# MOSFET_Driver_8_24_2505D.net
KiCad netlist of a schematic drawn in EAGLE
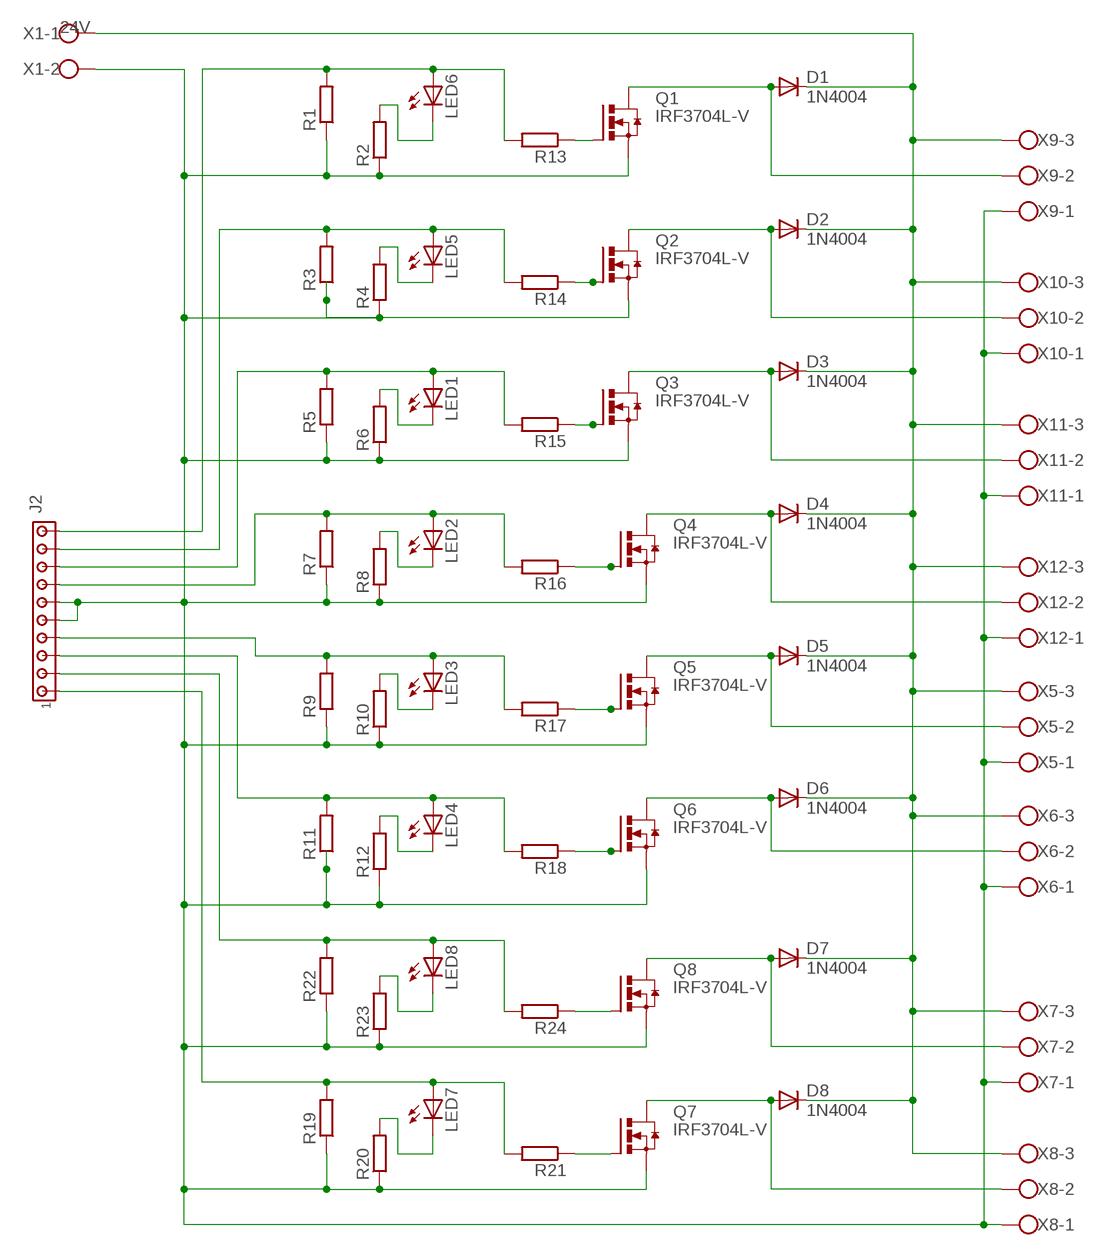
[diagram p0: schematic, sheet 1]

(export (version "E")
  (design (tool "Eeschema 10.0.6"))
  (components
    (comp (ref "D1")
      (value "1N4004")
      (footprint "eagle-import:DO41-10")
      (libsource (lib "eagle-import") (part "1N4004"))
    )
    (comp (ref "D2")
      (value "1N4004")
      (footprint "eagle-import:DO41-10")
      (libsource (lib "eagle-import") (part "1N4004"))
    )
    (comp (ref "D3")
      (value "1N4004")
      (footprint "eagle-import:DO41-10")
      (libsource (lib "eagle-import") (part "1N4004"))
    )
    (comp (ref "D4")
      (value "1N4004")
      (footprint "eagle-import:DO41-10")
      (libsource (lib "eagle-import") (part "1N4004"))
    )
    (comp (ref "D5")
      (value "1N4004")
      (footprint "eagle-import:DO41-10")
      (libsource (lib "eagle-import") (part "1N4004"))
    )
    (comp (ref "D6")
      (value "1N4004")
      (footprint "eagle-import:DO41-10")
      (libsource (lib "eagle-import") (part "1N4004"))
    )
    (comp (ref "D7")
      (value "1N4004")
      (footprint "eagle-import:DO41-10")
      (libsource (lib "eagle-import") (part "1N4004"))
    )
    (comp (ref "D8")
      (value "1N4004")
      (footprint "eagle-import:DO41-10")
      (libsource (lib "eagle-import") (part "1N4004"))
    )
    (comp (ref "J2")
      (value "MTA10-156")
      (footprint "eagle-import:1X10MTA")
      (libsource (lib "eagle-import") (part "MTA10-156"))
    )
    (comp (ref "LED1")
      (value "LED5MM")
      (footprint "eagle-import:LED5MM")
      (libsource (lib "eagle-import") (part "LED5MM"))
    )
    (comp (ref "LED2")
      (value "LED5MM")
      (footprint "eagle-import:LED5MM")
      (libsource (lib "eagle-import") (part "LED5MM"))
    )
    (comp (ref "LED3")
      (value "LED5MM")
      (footprint "eagle-import:LED5MM")
      (libsource (lib "eagle-import") (part "LED5MM"))
    )
    (comp (ref "LED4")
      (value "LED5MM")
      (footprint "eagle-import:LED5MM")
      (libsource (lib "eagle-import") (part "LED5MM"))
    )
    (comp (ref "LED5")
      (value "LED5MM")
      (footprint "eagle-import:LED5MM")
      (libsource (lib "eagle-import") (part "LED5MM"))
    )
    (comp (ref "LED6")
      (value "LED5MM")
      (footprint "eagle-import:LED5MM")
      (libsource (lib "eagle-import") (part "LED5MM"))
    )
    (comp (ref "LED7")
      (value "LED5MM")
      (footprint "eagle-import:LED5MM")
      (libsource (lib "eagle-import") (part "LED5MM"))
    )
    (comp (ref "LED8")
      (value "LED5MM")
      (footprint "eagle-import:LED5MM")
      (libsource (lib "eagle-import") (part "LED5MM"))
    )
    (comp (ref "Q1")
      (value "IRF3704L-V")
      (footprint "eagle-import:TO262-V")
      (libsource (lib "eagle-import") (part "IRF3704L-V"))
    )
    (comp (ref "Q2")
      (value "IRF3704L-V")
      (footprint "eagle-import:TO262-V")
      (libsource (lib "eagle-import") (part "IRF3704L-V"))
    )
    (comp (ref "Q3")
      (value "IRF3704L-V")
      (footprint "eagle-import:TO262-V")
      (libsource (lib "eagle-import") (part "IRF3704L-V"))
    )
    (comp (ref "Q4")
      (value "IRF3704L-V")
      (footprint "eagle-import:TO262-V")
      (libsource (lib "eagle-import") (part "IRF3704L-V"))
    )
    (comp (ref "Q5")
      (value "IRF3704L-V")
      (footprint "eagle-import:TO262-V")
      (libsource (lib "eagle-import") (part "IRF3704L-V"))
    )
    (comp (ref "Q6")
      (value "IRF3704L-V")
      (footprint "eagle-import:TO262-V")
      (libsource (lib "eagle-import") (part "IRF3704L-V"))
    )
    (comp (ref "Q7")
      (value "IRF3704L-V")
      (footprint "eagle-import:TO262-V")
      (libsource (lib "eagle-import") (part "IRF3704L-V"))
    )
    (comp (ref "Q8")
      (value "IRF3704L-V")
      (footprint "eagle-import:TO262-V")
      (libsource (lib "eagle-import") (part "IRF3704L-V"))
    )
    (comp (ref "R1")
      (value "R-EU_0207/10")
      (footprint "eagle-import:0207_10")
      (libsource (lib "eagle-import") (part "R-EU_0207/10"))
    )
    (comp (ref "R2")
      (value "R-EU_0207/10")
      (footprint "eagle-import:0207_10")
      (libsource (lib "eagle-import") (part "R-EU_0207/10"))
    )
    (comp (ref "R3")
      (value "R-EU_0207/10")
      (footprint "eagle-import:0207_10")
      (libsource (lib "eagle-import") (part "R-EU_0207/10"))
    )
    (comp (ref "R4")
      (value "R-EU_0207/10")
      (footprint "eagle-import:0207_10")
      (libsource (lib "eagle-import") (part "R-EU_0207/10"))
    )
    (comp (ref "R5")
      (value "R-EU_0207/10")
      (footprint "eagle-import:0207_10")
      (libsource (lib "eagle-import") (part "R-EU_0207/10"))
    )
    (comp (ref "R6")
      (value "R-EU_0207/10")
      (footprint "eagle-import:0207_10")
      (libsource (lib "eagle-import") (part "R-EU_0207/10"))
    )
    (comp (ref "R7")
      (value "R-EU_0207/10")
      (footprint "eagle-import:0207_10")
      (libsource (lib "eagle-import") (part "R-EU_0207/10"))
    )
    (comp (ref "R8")
      (value "R-EU_0207/10")
      (footprint "eagle-import:0207_10")
      (libsource (lib "eagle-import") (part "R-EU_0207/10"))
    )
    (comp (ref "R9")
      (value "R-EU_0207/10")
      (footprint "eagle-import:0207_10")
      (libsource (lib "eagle-import") (part "R-EU_0207/10"))
    )
    (comp (ref "R10")
      (value "R-EU_0207/10")
      (footprint "eagle-import:0207_10")
      (libsource (lib "eagle-import") (part "R-EU_0207/10"))
    )
    (comp (ref "R11")
      (value "R-EU_0207/10")
      (footprint "eagle-import:0207_10")
      (libsource (lib "eagle-import") (part "R-EU_0207/10"))
    )
    (comp (ref "R12")
      (value "R-EU_0207/10")
      (footprint "eagle-import:0207_10")
      (libsource (lib "eagle-import") (part "R-EU_0207/10"))
    )
    (comp (ref "R13")
      (value "R-EU_0207/10")
      (footprint "eagle-import:0207_10")
      (libsource (lib "eagle-import") (part "R-EU_0207/10"))
    )
    (comp (ref "R14")
      (value "R-EU_0207/10")
      (footprint "eagle-import:0207_10")
      (libsource (lib "eagle-import") (part "R-EU_0207/10"))
    )
    (comp (ref "R15")
      (value "R-EU_0207/10")
      (footprint "eagle-import:0207_10")
      (libsource (lib "eagle-import") (part "R-EU_0207/10"))
    )
    (comp (ref "R16")
      (value "R-EU_0207/10")
      (footprint "eagle-import:0207_10")
      (libsource (lib "eagle-import") (part "R-EU_0207/10"))
    )
    (comp (ref "R17")
      (value "R-EU_0207/10")
      (footprint "eagle-import:0207_10")
      (libsource (lib "eagle-import") (part "R-EU_0207/10"))
    )
    (comp (ref "R18")
      (value "R-EU_0207/10")
      (footprint "eagle-import:0207_10")
      (libsource (lib "eagle-import") (part "R-EU_0207/10"))
    )
    (comp (ref "R19")
      (value "R-EU_0207/10")
      (footprint "eagle-import:0207_10")
      (libsource (lib "eagle-import") (part "R-EU_0207/10"))
    )
    (comp (ref "R20")
      (value "R-EU_0207/10")
      (footprint "eagle-import:0207_10")
      (libsource (lib "eagle-import") (part "R-EU_0207/10"))
    )
    (comp (ref "R21")
      (value "R-EU_0207/10")
      (footprint "eagle-import:0207_10")
      (libsource (lib "eagle-import") (part "R-EU_0207/10"))
    )
    (comp (ref "R22")
      (value "R-EU_0207/10")
      (footprint "eagle-import:0207_10")
      (libsource (lib "eagle-import") (part "R-EU_0207/10"))
    )
    (comp (ref "R23")
      (value "R-EU_0207/10")
      (footprint "eagle-import:0207_10")
      (libsource (lib "eagle-import") (part "R-EU_0207/10"))
    )
    (comp (ref "R24")
      (value "R-EU_0207/10")
      (footprint "eagle-import:0207_10")
      (libsource (lib "eagle-import") (part "R-EU_0207/10"))
    )
    (comp (ref "X1")
      (value "W237-102")
      (footprint "eagle-import:W237-102")
      (libsource (lib "eagle-import") (part "W237-102"))
    )
    (comp (ref "X5")
      (value "W237-103")
      (footprint "eagle-import:W237-103")
      (libsource (lib "eagle-import") (part "W237-103"))
    )
    (comp (ref "X6")
      (value "W237-103")
      (footprint "eagle-import:W237-103")
      (libsource (lib "eagle-import") (part "W237-103"))
    )
    (comp (ref "X7")
      (value "W237-103")
      (footprint "eagle-import:W237-103")
      (libsource (lib "eagle-import") (part "W237-103"))
    )
    (comp (ref "X8")
      (value "W237-103")
      (footprint "eagle-import:W237-103")
      (libsource (lib "eagle-import") (part "W237-103"))
    )
    (comp (ref "X9")
      (value "W237-103")
      (footprint "eagle-import:W237-103")
      (libsource (lib "eagle-import") (part "W237-103"))
    )
    (comp (ref "X10")
      (value "W237-103")
      (footprint "eagle-import:W237-103")
      (libsource (lib "eagle-import") (part "W237-103"))
    )
    (comp (ref "X11")
      (value "W237-103")
      (footprint "eagle-import:W237-103")
      (libsource (lib "eagle-import") (part "W237-103"))
    )
    (comp (ref "X12")
      (value "W237-103")
      (footprint "eagle-import:W237-103")
      (libsource (lib "eagle-import") (part "W237-103"))
    )
  )
  (nets
    (net (code "1") (name "Net-(J2-Pad1)") (class "Default")
      (node (ref "J2") (pin "1") (pinfunction "1_1") (pintype "passive"))
      (node (ref "LED7") (pin "A") (pinfunction "A_A") (pintype "passive"))
      (node (ref "R19") (pin "2") (pinfunction "2_2") (pintype "passive"))
      (node (ref "R21") (pin "2") (pinfunction "2_2") (pintype "passive"))
    )
    (net (code "2") (name "Net-(J2-Pad2)") (class "Default")
      (node (ref "J2") (pin "2") (pinfunction "2_2") (pintype "passive"))
      (node (ref "LED8") (pin "A") (pinfunction "A_A") (pintype "passive"))
      (node (ref "R22") (pin "2") (pinfunction "2_2") (pintype "passive"))
      (node (ref "R24") (pin "2") (pinfunction "2_2") (pintype "passive"))
    )
    (net (code "3") (name "Net-(J2-Pad3)") (class "Default")
      (node (ref "J2") (pin "3") (pinfunction "3_3") (pintype "passive"))
      (node (ref "LED4") (pin "A") (pinfunction "A_A") (pintype "passive"))
      (node (ref "R11") (pin "2") (pinfunction "2_2") (pintype "passive"))
      (node (ref "R18") (pin "2") (pinfunction "2_2") (pintype "passive"))
    )
    (net (code "4") (name "Net-(J2-Pad4)") (class "Default")
      (node (ref "J2") (pin "4") (pinfunction "4_4") (pintype "passive"))
      (node (ref "LED3") (pin "A") (pinfunction "A_A") (pintype "passive"))
      (node (ref "R17") (pin "2") (pinfunction "2_2") (pintype "passive"))
      (node (ref "R9") (pin "2") (pinfunction "2_2") (pintype "passive"))
    )
    (net (code "5") (name "Net-(J2-Pad7)") (class "Default")
      (node (ref "J2") (pin "7") (pinfunction "7_7") (pintype "passive"))
      (node (ref "LED2") (pin "A") (pinfunction "A_A") (pintype "passive"))
      (node (ref "R16") (pin "2") (pinfunction "2_2") (pintype "passive"))
      (node (ref "R7") (pin "2") (pinfunction "2_2") (pintype "passive"))
    )
    (net (code "6") (name "Net-(J2-Pad8)") (class "Default")
      (node (ref "J2") (pin "8") (pinfunction "8_8") (pintype "passive"))
      (node (ref "LED1") (pin "A") (pinfunction "A_A") (pintype "passive"))
      (node (ref "R15") (pin "2") (pinfunction "2_2") (pintype "passive"))
      (node (ref "R5") (pin "2") (pinfunction "2_2") (pintype "passive"))
    )
    (net (code "7") (name "Net-(J2-Pad9)") (class "Default")
      (node (ref "J2") (pin "9") (pinfunction "9_9") (pintype "passive"))
      (node (ref "LED5") (pin "A") (pinfunction "A_A") (pintype "passive"))
      (node (ref "R14") (pin "2") (pinfunction "2_2") (pintype "passive"))
      (node (ref "R3") (pin "2") (pinfunction "2_2") (pintype "passive"))
    )
    (net (code "8") (name "Net-(J2-Pad10)") (class "Default")
      (node (ref "J2") (pin "10") (pinfunction "10_10") (pintype "passive"))
      (node (ref "LED6") (pin "A") (pinfunction "A_A") (pintype "passive"))
      (node (ref "R1") (pin "2") (pinfunction "2_2") (pintype "passive"))
      (node (ref "R13") (pin "2") (pinfunction "2_2") (pintype "passive"))
    )
    (net (code "9") (name "Net-(LED1-C)") (class "Default")
      (node (ref "LED1") (pin "K") (pinfunction "C_K") (pintype "passive"))
      (node (ref "R6") (pin "2") (pinfunction "2_2") (pintype "passive"))
    )
    (net (code "10") (name "Net-(LED2-C)") (class "Default")
      (node (ref "LED2") (pin "K") (pinfunction "C_K") (pintype "passive"))
      (node (ref "R8") (pin "2") (pinfunction "2_2") (pintype "passive"))
    )
    (net (code "11") (name "Net-(LED3-C)") (class "Default")
      (node (ref "LED3") (pin "K") (pinfunction "C_K") (pintype "passive"))
      (node (ref "R10") (pin "2") (pinfunction "2_2") (pintype "passive"))
    )
    (net (code "12") (name "Net-(LED4-C)") (class "Default")
      (node (ref "LED4") (pin "K") (pinfunction "C_K") (pintype "passive"))
      (node (ref "R12") (pin "2") (pinfunction "2_2") (pintype "passive"))
    )
    (net (code "13") (name "Net-(LED5-C)") (class "Default")
      (node (ref "LED5") (pin "K") (pinfunction "C_K") (pintype "passive"))
      (node (ref "R4") (pin "2") (pinfunction "2_2") (pintype "passive"))
    )
    (net (code "14") (name "Net-(LED6-C)") (class "Default")
      (node (ref "LED6") (pin "K") (pinfunction "C_K") (pintype "passive"))
      (node (ref "R2") (pin "2") (pinfunction "2_2") (pintype "passive"))
    )
    (net (code "15") (name "Net-(LED7-C)") (class "Default")
      (node (ref "LED7") (pin "K") (pinfunction "C_K") (pintype "passive"))
      (node (ref "R20") (pin "2") (pinfunction "2_2") (pintype "passive"))
    )
    (net (code "16") (name "Net-(LED8-C)") (class "Default")
      (node (ref "LED8") (pin "K") (pinfunction "C_K") (pintype "passive"))
      (node (ref "R23") (pin "2") (pinfunction "2_2") (pintype "passive"))
    )
    (net (code "17") (name "Net-(Q1-D)") (class "Default")
      (node (ref "D1") (pin "A") (pinfunction "A_A") (pintype "passive"))
      (node (ref "Q1") (pin "2") (pinfunction "D_2") (pintype "passive"))
      (node (ref "X9") (pin "2") (pinfunction "KL_2") (pintype "passive"))
    )
    (net (code "18") (name "Net-(Q1-G)") (class "Default")
      (node (ref "Q1") (pin "1") (pinfunction "G_1") (pintype "passive"))
      (node (ref "R13") (pin "1") (pinfunction "1_1") (pintype "passive"))
    )
    (net (code "19") (name "Net-(Q1-S)") (class "Default")
      (node (ref "J2") (pin "5") (pinfunction "5_5") (pintype "passive"))
      (node (ref "J2") (pin "6") (pinfunction "6_6") (pintype "passive"))
      (node (ref "Q1") (pin "3") (pinfunction "S_3") (pintype "passive"))
      (node (ref "Q2") (pin "3") (pinfunction "S_3") (pintype "passive"))
      (node (ref "Q3") (pin "3") (pinfunction "S_3") (pintype "passive"))
      (node (ref "Q4") (pin "3") (pinfunction "S_3") (pintype "passive"))
      (node (ref "Q5") (pin "3") (pinfunction "S_3") (pintype "passive"))
      (node (ref "Q6") (pin "3") (pinfunction "S_3") (pintype "passive"))
      (node (ref "Q7") (pin "3") (pinfunction "S_3") (pintype "passive"))
      (node (ref "Q8") (pin "3") (pinfunction "S_3") (pintype "passive"))
      (node (ref "R1") (pin "1") (pinfunction "1_1") (pintype "passive"))
      (node (ref "R10") (pin "1") (pinfunction "1_1") (pintype "passive"))
      (node (ref "R11") (pin "1") (pinfunction "1_1") (pintype "passive"))
      (node (ref "R12") (pin "1") (pinfunction "1_1") (pintype "passive"))
      (node (ref "R19") (pin "1") (pinfunction "1_1") (pintype "passive"))
      (node (ref "R2") (pin "1") (pinfunction "1_1") (pintype "passive"))
      (node (ref "R20") (pin "1") (pinfunction "1_1") (pintype "passive"))
      (node (ref "R22") (pin "1") (pinfunction "1_1") (pintype "passive"))
      (node (ref "R23") (pin "1") (pinfunction "1_1") (pintype "passive"))
      (node (ref "R3") (pin "1") (pinfunction "1_1") (pintype "passive"))
      (node (ref "R4") (pin "1") (pinfunction "1_1") (pintype "passive"))
      (node (ref "R5") (pin "1") (pinfunction "1_1") (pintype "passive"))
      (node (ref "R6") (pin "1") (pinfunction "1_1") (pintype "passive"))
      (node (ref "R7") (pin "1") (pinfunction "1_1") (pintype "passive"))
      (node (ref "R8") (pin "1") (pinfunction "1_1") (pintype "passive"))
      (node (ref "R9") (pin "1") (pinfunction "1_1") (pintype "passive"))
      (node (ref "X1") (pin "2") (pinfunction "KL_2") (pintype "passive"))
      (node (ref "X10") (pin "1") (pinfunction "KL_1") (pintype "passive"))
      (node (ref "X11") (pin "1") (pinfunction "KL_1") (pintype "passive"))
      (node (ref "X12") (pin "1") (pinfunction "KL_1") (pintype "passive"))
      (node (ref "X5") (pin "1") (pinfunction "KL_1") (pintype "passive"))
      (node (ref "X6") (pin "1") (pinfunction "KL_1") (pintype "passive"))
      (node (ref "X7") (pin "1") (pinfunction "KL_1") (pintype "passive"))
      (node (ref "X8") (pin "1") (pinfunction "KL_1") (pintype "passive"))
      (node (ref "X9") (pin "1") (pinfunction "KL_1") (pintype "passive"))
    )
    (net (code "20") (name "Net-(Q2-D)") (class "Default")
      (node (ref "D2") (pin "A") (pinfunction "A_A") (pintype "passive"))
      (node (ref "Q2") (pin "2") (pinfunction "D_2") (pintype "passive"))
      (node (ref "X10") (pin "2") (pinfunction "KL_2") (pintype "passive"))
    )
    (net (code "21") (name "Net-(Q2-G)") (class "Default")
      (node (ref "Q2") (pin "1") (pinfunction "G_1") (pintype "passive"))
      (node (ref "R14") (pin "1") (pinfunction "1_1") (pintype "passive"))
    )
    (net (code "22") (name "Net-(Q3-D)") (class "Default")
      (node (ref "D3") (pin "A") (pinfunction "A_A") (pintype "passive"))
      (node (ref "Q3") (pin "2") (pinfunction "D_2") (pintype "passive"))
      (node (ref "X11") (pin "2") (pinfunction "KL_2") (pintype "passive"))
    )
    (net (code "23") (name "Net-(Q3-G)") (class "Default")
      (node (ref "Q3") (pin "1") (pinfunction "G_1") (pintype "passive"))
      (node (ref "R15") (pin "1") (pinfunction "1_1") (pintype "passive"))
    )
    (net (code "24") (name "Net-(Q4-D)") (class "Default")
      (node (ref "D4") (pin "A") (pinfunction "A_A") (pintype "passive"))
      (node (ref "Q4") (pin "2") (pinfunction "D_2") (pintype "passive"))
      (node (ref "X12") (pin "2") (pinfunction "KL_2") (pintype "passive"))
    )
    (net (code "25") (name "Net-(Q4-G)") (class "Default")
      (node (ref "Q4") (pin "1") (pinfunction "G_1") (pintype "passive"))
      (node (ref "R16") (pin "1") (pinfunction "1_1") (pintype "passive"))
    )
    (net (code "26") (name "Net-(Q5-D)") (class "Default")
      (node (ref "D5") (pin "A") (pinfunction "A_A") (pintype "passive"))
      (node (ref "Q5") (pin "2") (pinfunction "D_2") (pintype "passive"))
      (node (ref "X5") (pin "2") (pinfunction "KL_2") (pintype "passive"))
    )
    (net (code "27") (name "Net-(Q5-G)") (class "Default")
      (node (ref "Q5") (pin "1") (pinfunction "G_1") (pintype "passive"))
      (node (ref "R17") (pin "1") (pinfunction "1_1") (pintype "passive"))
    )
    (net (code "28") (name "Net-(Q6-D)") (class "Default")
      (node (ref "D6") (pin "A") (pinfunction "A_A") (pintype "passive"))
      (node (ref "Q6") (pin "2") (pinfunction "D_2") (pintype "passive"))
      (node (ref "X6") (pin "2") (pinfunction "KL_2") (pintype "passive"))
    )
    (net (code "29") (name "Net-(Q6-G)") (class "Default")
      (node (ref "Q6") (pin "1") (pinfunction "G_1") (pintype "passive"))
      (node (ref "R18") (pin "1") (pinfunction "1_1") (pintype "passive"))
    )
    (net (code "30") (name "Net-(Q7-D)") (class "Default")
      (node (ref "D8") (pin "A") (pinfunction "A_A") (pintype "passive"))
      (node (ref "Q7") (pin "2") (pinfunction "D_2") (pintype "passive"))
      (node (ref "X8") (pin "2") (pinfunction "KL_2") (pintype "passive"))
    )
    (net (code "31") (name "Net-(Q7-G)") (class "Default")
      (node (ref "Q7") (pin "1") (pinfunction "G_1") (pintype "passive"))
      (node (ref "R21") (pin "1") (pinfunction "1_1") (pintype "passive"))
    )
    (net (code "32") (name "Net-(Q8-D)") (class "Default")
      (node (ref "D7") (pin "A") (pinfunction "A_A") (pintype "passive"))
      (node (ref "Q8") (pin "2") (pinfunction "D_2") (pintype "passive"))
      (node (ref "X7") (pin "2") (pinfunction "KL_2") (pintype "passive"))
    )
    (net (code "33") (name "Net-(Q8-G)") (class "Default")
      (node (ref "Q8") (pin "1") (pinfunction "G_1") (pintype "passive"))
      (node (ref "R24") (pin "1") (pinfunction "1_1") (pintype "passive"))
    )
    (net (code "34") (name "Net-(X10C-KL)") (class "Default")
      (node (ref "D1") (pin "C") (pinfunction "C_C") (pintype "passive"))
      (node (ref "D2") (pin "C") (pinfunction "C_C") (pintype "passive"))
      (node (ref "D3") (pin "C") (pinfunction "C_C") (pintype "passive"))
      (node (ref "D4") (pin "C") (pinfunction "C_C") (pintype "passive"))
      (node (ref "D5") (pin "C") (pinfunction "C_C") (pintype "passive"))
      (node (ref "D6") (pin "C") (pinfunction "C_C") (pintype "passive"))
      (node (ref "D7") (pin "C") (pinfunction "C_C") (pintype "passive"))
      (node (ref "D8") (pin "C") (pinfunction "C_C") (pintype "passive"))
      (node (ref "X1") (pin "1") (pinfunction "KL_1") (pintype "passive"))
      (node (ref "X10") (pin "3") (pinfunction "KL_3") (pintype "passive"))
      (node (ref "X11") (pin "3") (pinfunction "KL_3") (pintype "passive"))
      (node (ref "X12") (pin "3") (pinfunction "KL_3") (pintype "passive"))
      (node (ref "X5") (pin "3") (pinfunction "KL_3") (pintype "passive"))
      (node (ref "X6") (pin "3") (pinfunction "KL_3") (pintype "passive"))
      (node (ref "X7") (pin "3") (pinfunction "KL_3") (pintype "passive"))
      (node (ref "X8") (pin "3") (pinfunction "KL_3") (pintype "passive"))
      (node (ref "X9") (pin "3") (pinfunction "KL_3") (pintype "passive"))
    )
  )
)
